# PS_Simulation.net
KiCad netlist of a schematic drawn in Altium Designer
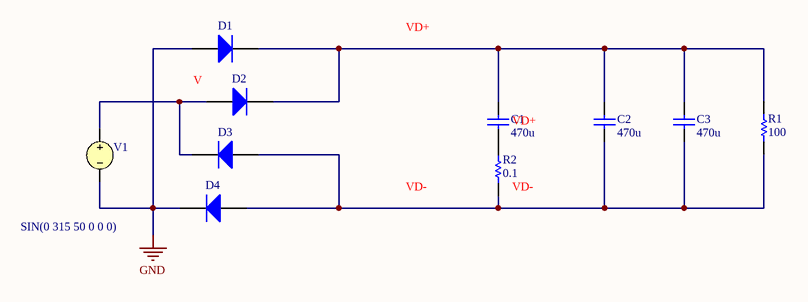
[diagram p0: PS_Simulation.SchDoc]

(export (version "E")
  (design (tool "Eeschema 10.0.6"))
  (components
    (comp (ref "C1")
      (value "470u")
      (description "Capacitor")
      (libsource (lib "Simulation Generic Components") (part "Capacitor"))
    )
    (comp (ref "C2")
      (value "470u")
      (description "Capacitor")
      (libsource (lib "Simulation Generic Components") (part "Capacitor"))
    )
    (comp (ref "C3")
      (value "470u")
      (description "Capacitor")
      (libsource (lib "Simulation Generic Components") (part "Capacitor"))
    )
    (comp (ref "D1") (value "Diode") (libsource (lib "Simulation Generic Components") (part "Diode")))
    (comp (ref "D2") (value "Diode") (libsource (lib "Simulation Generic Components") (part "Diode")))
    (comp (ref "D3") (value "Diode") (libsource (lib "Simulation Generic Components") (part "Diode")))
    (comp (ref "D4") (value "Diode") (libsource (lib "Simulation Generic Components") (part "Diode")))
    (comp (ref "R1")
      (value "100")
      (description "Resistor")
      (libsource (lib "Simulation Generic Components") (part "Resistor"))
    )
    (comp (ref "R2")
      (value "0.1")
      (description "Resistor")
      (libsource (lib "Simulation Generic Components") (part "Resistor"))
    )
    (comp (ref "V1")
      (value "SIN(0 315 50 0 0 0)")
      (description "Voltage Source")
      (fields (field (name "PUBLISHER") "Altium Limited"))
      (libsource (lib "Simulation Generic Components") (part "VSRC"))
    )
  )
  (nets
    (net (code "1") (name "GND") (class "Default")
      (node (ref "D1") (pin "1") (pinfunction "A_1") (pintype "passive"))
      (node (ref "D4") (pin "2") (pinfunction "K_2") (pintype "passive"))
      (node (ref "V1") (pin "2") (pinfunction "2_2") (pintype "passive"))
    )
    (net (code "2") (name "Net-(C1-Pad2)") (class "Default")
      (node (ref "C1") (pin "2") (pinfunction "2_2") (pintype "passive"))
      (node (ref "R2") (pin "2") (pinfunction "2_2") (pintype "passive"))
    )
    (net (code "3") (name "Net-(D1-K)") (class "Default")
      (node (ref "C1") (pin "1") (pinfunction "1_1") (pintype "passive"))
      (node (ref "C2") (pin "1") (pinfunction "1_1") (pintype "passive"))
      (node (ref "C3") (pin "1") (pinfunction "1_1") (pintype "passive"))
      (node (ref "D1") (pin "2") (pinfunction "K_2") (pintype "passive"))
      (node (ref "D2") (pin "2") (pinfunction "K_2") (pintype "passive"))
      (node (ref "R1") (pin "2") (pinfunction "2_2") (pintype "passive"))
    )
    (net (code "4") (name "Net-(D2-A)") (class "Default")
      (node (ref "D2") (pin "1") (pinfunction "A_1") (pintype "passive"))
      (node (ref "D3") (pin "2") (pinfunction "K_2") (pintype "passive"))
      (node (ref "V1") (pin "1") (pinfunction "1_1") (pintype "passive"))
    )
    (net (code "5") (name "Net-(D3-A)") (class "Default")
      (node (ref "C2") (pin "2") (pinfunction "2_2") (pintype "passive"))
      (node (ref "C3") (pin "2") (pinfunction "2_2") (pintype "passive"))
      (node (ref "D3") (pin "1") (pinfunction "A_1") (pintype "passive"))
      (node (ref "D4") (pin "1") (pinfunction "A_1") (pintype "passive"))
      (node (ref "R1") (pin "1") (pinfunction "1_1") (pintype "passive"))
      (node (ref "R2") (pin "1") (pinfunction "1_1") (pintype "passive"))
    )
  )
)
